# sensors_board.net
KiCad netlist of a schematic drawn in EAGLE
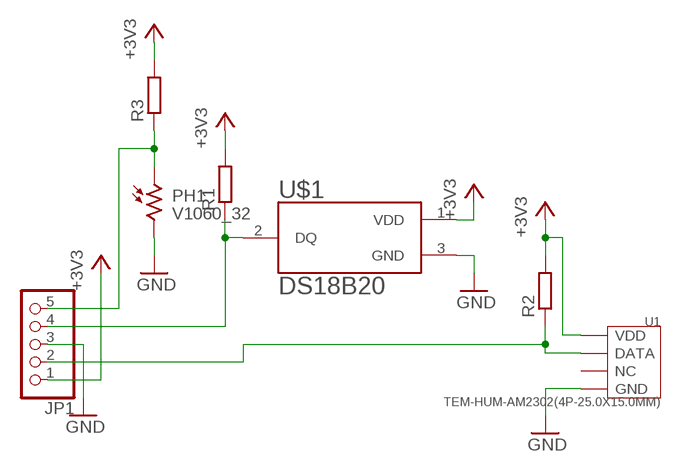
[diagram p0: schematic, sheet 1]

(export (version "E")
  (design (tool "Eeschema 10.0.6"))
  (components
    (comp (ref "JP1")
      (value "PINHD-1X5/90")
      (footprint "eagle-import:1X05_90")
      (libsource (lib "eagle-import") (part "PINHD-1X5/90"))
    )
    (comp (ref "PH1")
      (value "V1060_32")
      (footprint "eagle-import:TO-5_V10")
      (libsource (lib "eagle-import") (part "?1060V_32"))
    )
    (comp (ref "R1")
      (value "R-EU_R1206")
      (footprint "eagle-import:R1206")
      (libsource (lib "eagle-import") (part "R-EU_R1206"))
    )
    (comp (ref "R2")
      (value "R-EU_R1206")
      (footprint "eagle-import:R1206")
      (libsource (lib "eagle-import") (part "R-EU_R1206"))
    )
    (comp (ref "R3")
      (value "R-EU_R1206")
      (footprint "eagle-import:R1206")
      (libsource (lib "eagle-import") (part "R-EU_R1206"))
    )
    (comp (ref "U$1")
      (value "DS18B20")
      (footprint "eagle-import:TO92-")
      (libsource (lib "eagle-import") (part "DS18B20"))
    )
    (comp (ref "U1")
      (value "TEM-HUM-AM2302(4P-25.0X15.0MM)")
      (footprint "eagle-import:SNR4-2.54-25.0X15.0X7.0MM")
      (fields (field (name "MF") "MCM Electronics") (field (name "MP") "AM2302"))
      (libsource (lib "eagle-import") (part "TEM-HUM-AM2302(4P-25.0X15.0MM)"))
    )
  )
  (nets
    (net (code "1") (name "+3V3") (class "Default")
      (node (ref "JP1") (pin "1") (pinfunction "1_1") (pintype "passive"))
      (node (ref "R1") (pin "2") (pinfunction "2_2") (pintype "passive"))
      (node (ref "R2") (pin "2") (pinfunction "2_2") (pintype "passive"))
      (node (ref "R3") (pin "2") (pinfunction "2_2") (pintype "passive"))
      (node (ref "U$1") (pin "1") (pinfunction "VDD_1") (pintype "power_in"))
      (node (ref "U1") (pin "P$1") (pinfunction "VDD_P$1") (pintype "power_in"))
    )
    (net (code "2") (name "GND") (class "Default")
      (node (ref "JP1") (pin "3") (pinfunction "3_3") (pintype "passive"))
      (node (ref "PH1") (pin "2") (pinfunction "2_2") (pintype "passive"))
      (node (ref "U$1") (pin "3") (pinfunction "GND_3") (pintype "power_in"))
      (node (ref "U1") (pin "P$4") (pinfunction "GND_P$4") (pintype "power_in"))
    )
    (net (code "3") (name "Net-(JP1-Pad5)") (class "Default")
      (node (ref "JP1") (pin "5") (pinfunction "5_5") (pintype "passive"))
      (node (ref "PH1") (pin "1") (pinfunction "1_1") (pintype "passive"))
      (node (ref "R3") (pin "1") (pinfunction "1_1") (pintype "passive"))
    )
    (net (code "4") (name "Net-(U$1-DQ)") (class "Default")
      (node (ref "JP1") (pin "4") (pinfunction "4_4") (pintype "passive"))
      (node (ref "R1") (pin "1") (pinfunction "1_1") (pintype "passive"))
      (node (ref "U$1") (pin "2") (pinfunction "DQ_2") (pintype "bidirectional"))
    )
    (net (code "5") (name "Net-(U1-DATA)") (class "Default")
      (node (ref "JP1") (pin "2") (pinfunction "2_2") (pintype "passive"))
      (node (ref "R2") (pin "1") (pinfunction "1_1") (pintype "passive"))
      (node (ref "U1") (pin "P$2") (pinfunction "DATA_P$2") (pintype "bidirectional"))
    )
    (net (code "6") (name "unconnected-(U1-NC-PadP$3)") (class "Default")
      (node (ref "U1") (pin "P$3") (pinfunction "NC_P$3") (pintype "no_connect"))
    )
  )
)
